# Inverters_drives.net
KiCad netlist of a schematic drawn in Altium Designer
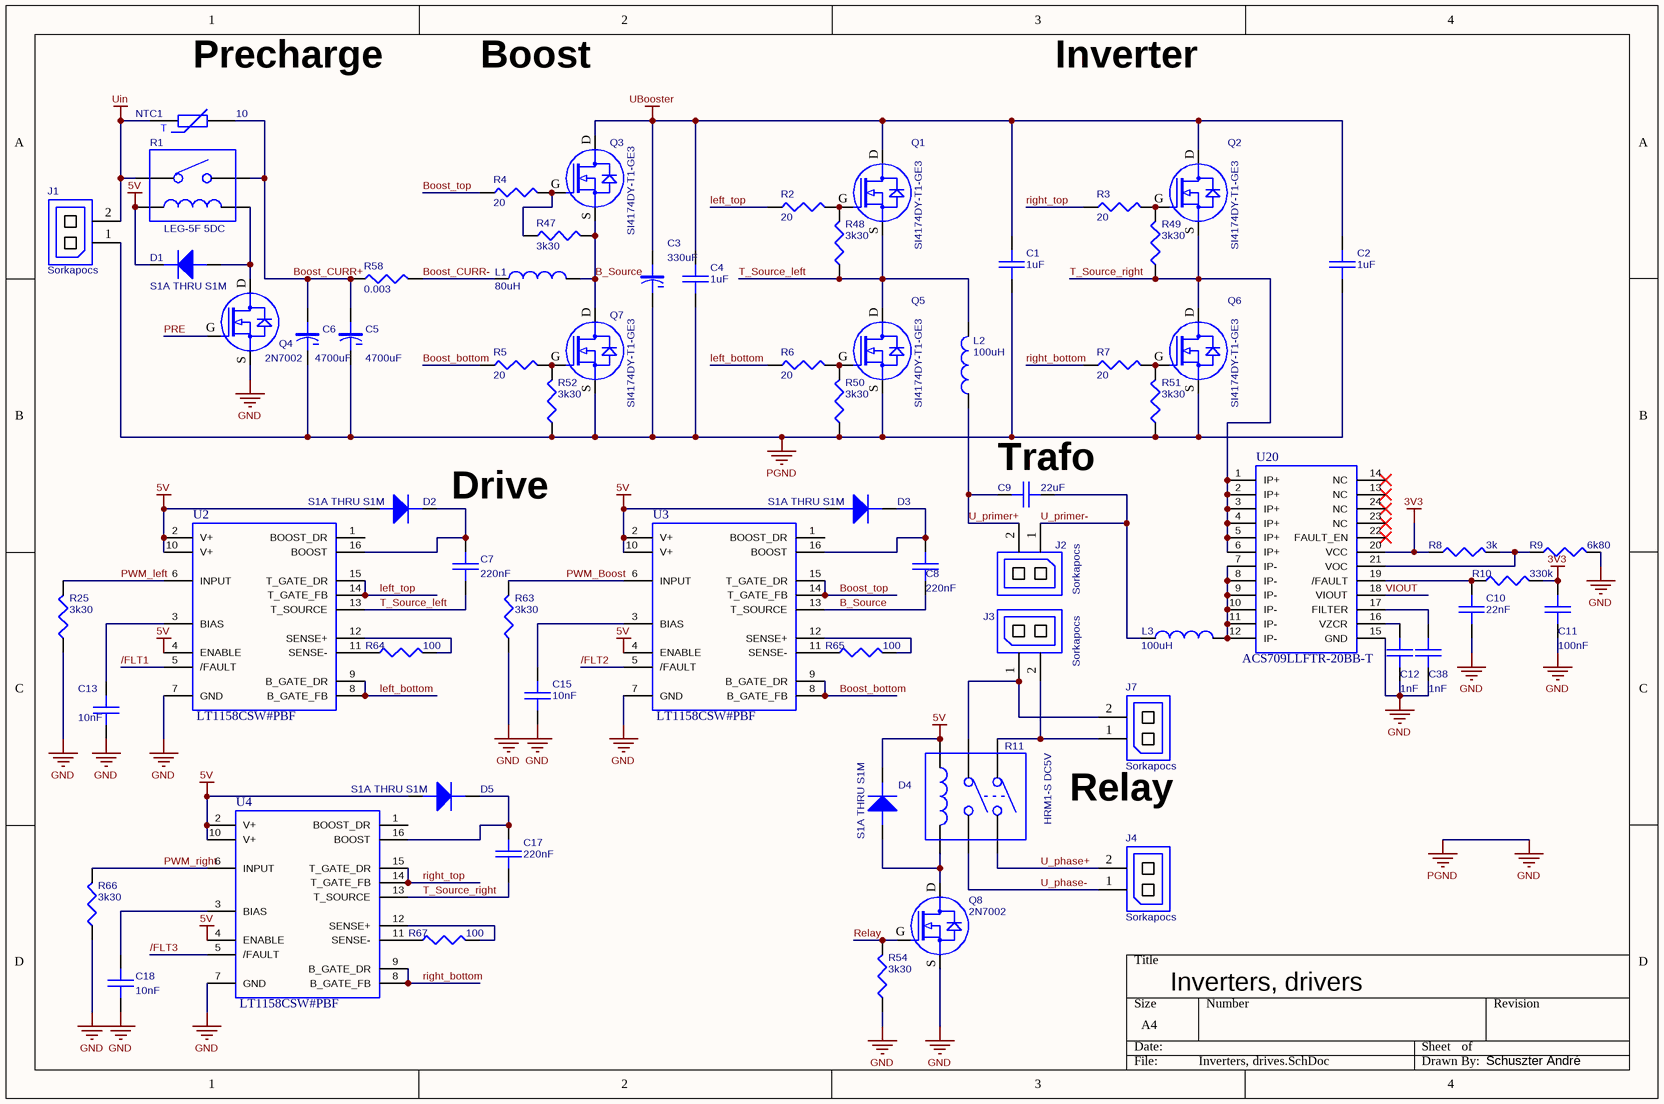
[diagram p0: Inverters, drives.SchDoc]

(export (version "E")
  (design (tool "Eeschema 10.0.6"))
  (components
    (comp (ref "C1")
      (value "1uF")
      (footprint "CAPC3216X07N")
      (description "2495497")
      (fields (field (name "PART NUMBER") "0805F105Z500CT"))
      (libsource (lib "Schlib1") (part "Csnubber"))
    )
    (comp (ref "C2")
      (value "1uF")
      (footprint "CAPC3216X07N")
      (description "2495497")
      (fields (field (name "PART NUMBER") "0805F105Z500CT"))
      (libsource (lib "Schlib1") (part "Csnubber"))
    )
    (comp (ref "C3")
      (value "330uF")
      (footprint "CAPAE116103X105N")
      (description "2611390")
      (fields (field (name "PART NUMBER") "MCVVT035M331GB3L"))
      (libsource (lib "PCB_PASSIVE") (part "CAPAE"))
    )
    (comp (ref "C4")
      (value "1uF")
      (footprint "CAPC3216X07N")
      (description "2495497")
      (fields (field (name "PART NUMBER") "GRM31CR6YA106KA12L"))
      (libsource (lib "Schlib1") (part "Csnubber"))
    )
    (comp (ref "C5")
      (value "4700uF")
      (footprint "CAPAE189170X165N")
      (description "2326365")
      (fields (field (name "PART NUMBER") "EEVFK1C472M"))
      (libsource (lib "PCB_PASSIVE") (part "CAPAE"))
    )
    (comp (ref "C6")
      (value "4700uF")
      (footprint "CAPAE189170X165N")
      (description "2326365")
      (fields (field (name "PART NUMBER") "EEVFK1C472M"))
      (libsource (lib "PCB_PASSIVE") (part "CAPAE"))
    )
    (comp (ref "C7")
      (value "220nF")
      (footprint "CAPC2012X06N")
      (description "82-03-85")
      (libsource (lib "PCB_PASSIVE") (part "CAPC"))
    )
    (comp (ref "C8")
      (value "220nF")
      (footprint "CAPC2012X06N")
      (description "82-03-85")
      (libsource (lib "PCB_PASSIVE") (part "CAPC"))
    )
    (comp (ref "C9")
      (value "22uF")
      (footprint "MKS4D052206F00KYSD")
      (description "07-06-83")
      (fields
        (field (name "PART NUMBER") "22uF 100V RM27.5 10% FOL MKS4 MKS4D052206F00KYSD (WIM) 15x26x31.5mm")
      )
      (libsource (lib "PCB_PASSIVE") (part "CAPC"))
    )
    (comp (ref "C10")
      (value "22nF")
      (footprint "CAPC2012X06N")
      (description "82-00-77")
      (libsource (lib "PCB_PASSIVE") (part "CAPC"))
    )
    (comp (ref "C11")
      (value "100nF")
      (footprint "CAPC2012X06N")
      (description "82-07-32")
      (libsource (lib "PCB_PASSIVE") (part "CAPC"))
    )
    (comp (ref "C12")
      (value "1nF")
      (footprint "CAPC2012X06N")
      (description "82-00-75")
      (libsource (lib "PCB_PASSIVE") (part "CAPC"))
    )
    (comp (ref "C13")
      (value "10nF")
      (footprint "CAPC2012X06N")
      (description "82-05-66")
      (libsource (lib "PCB_PASSIVE") (part "CAPC"))
    )
    (comp (ref "C15")
      (value "10nF")
      (footprint "CAPC2012X06N")
      (description "82-05-66")
      (libsource (lib "PCB_PASSIVE") (part "CAPC"))
    )
    (comp (ref "C17")
      (value "220nF")
      (footprint "CAPC2012X06N")
      (description "82-03-85")
      (libsource (lib "PCB_PASSIVE") (part "CAPC"))
    )
    (comp (ref "C18")
      (value "10nF")
      (footprint "CAPC2012X06N")
      (description "82-05-66")
      (libsource (lib "PCB_PASSIVE") (part "CAPC"))
    )
    (comp (ref "C38")
      (value "1nF")
      (footprint "CAPC2012X06N")
      (description "82-00-75")
      (libsource (lib "PCB_PASSIVE") (part "CAPC"))
    )
    (comp (ref "D1")
      (value "S1A THRU S1M")
      (footprint "DIOM4436X25N")
      (description "83-02-64")
      (fields (field (name "PART NUMBER") "1A 1000V DO-214AC RECT. S1M (YET) SMA"))
      (libsource (lib "Schlib1") (part "RELÉ_DIO"))
    )
    (comp (ref "D2")
      (value "S1A THRU S1M")
      (footprint "DIOM4436X25N")
      (description "83-02-64")
      (fields (field (name "PART NUMBER") "1A 1000V DO-214AC RECT. S1M (YET) SMA"))
      (libsource (lib "Schlib1") (part "RELÉ_DIO"))
    )
    (comp (ref "D3")
      (value "S1A THRU S1M")
      (footprint "DIOM4436X25N")
      (description "83-02-64")
      (fields (field (name "PART NUMBER") "1A 1000V DO-214AC RECT. S1M (YET) SMA"))
      (libsource (lib "Schlib1") (part "RELÉ_DIO"))
    )
    (comp (ref "D4")
      (value "S1A THRU S1M")
      (footprint "DIOM4436X25N")
      (description "83-02-64")
      (fields (field (name "PART NUMBER") "1A 1000V DO-214AC RECT. S1M (YET) SMA"))
      (libsource (lib "Schlib1") (part "RELÉ_DIO"))
    )
    (comp (ref "D5")
      (value "S1A THRU S1M")
      (footprint "DIOM4436X25N")
      (description "83-02-64")
      (fields (field (name "PART NUMBER") "1A 1000V DO-214AC RECT. S1M (YET) SMA"))
      (libsource (lib "Schlib1") (part "RELÉ_DIO"))
    )
    (comp (ref "J1")
      (value "Sorkapocs")
      (footprint "sorkapocs")
      (description "43-07-92")
      (fields (field (name "PART NUMBER") "SORKAPOCS 2 P RM5.08 CLL5.08/2 (STE) h=13.8mm LIFT.2.5mmř 24A"))
      (libsource (lib "Schlib1") (part "Sorkapocs"))
    )
    (comp (ref "J2")
      (value "Sorkapocs")
      (footprint "sorkapocs")
      (description "43-07-92")
      (fields (field (name "PART NUMBER") "SORKAPOCS 2 P RM5.08 CLL5.08/2 (STE) h=13.8mm LIFT.2.5mmř 24A"))
      (libsource (lib "") (part "Sorkapocs_1"))
    )
    (comp (ref "J3")
      (value "Sorkapocs")
      (footprint "sorkapocs")
      (description "43-07-92")
      (fields (field (name "PART NUMBER") "SORKAPOCS 2 P RM5.08 CLL5.08/2 (STE) h=13.8mm LIFT.2.5mmř 24A"))
      (libsource (lib "") (part "Sorkapocs_2"))
    )
    (comp (ref "J4")
      (value "Sorkapocs")
      (footprint "sorkapocs")
      (description "43-07-92")
      (fields (field (name "PART NUMBER") "SORKAPOCS 2 P RM5.08 CLL5.08/2 (STE) h=13.8mm LIFT.2.5mmř 24A"))
      (libsource (lib "") (part "Sorkapocs_2"))
    )
    (comp (ref "J7")
      (value "Sorkapocs")
      (footprint "sorkapocs")
      (description "43-07-92")
      (fields (field (name "PART NUMBER") "SORKAPOCS 2 P RM5.08 CLL5.08/2 (STE) h=13.8mm LIFT.2.5mmř 24A"))
      (libsource (lib "") (part "Sorkapocs_2"))
    )
    (comp (ref "L1") (value "80uH") (footprint "IND_160uH") (libsource (lib "PCB_PASSIVE") (part "IND")))
    (comp (ref "L2") (value "100uH") (footprint "IND_160uH") (libsource (lib "PCB_PASSIVE") (part "IND")))
    (comp (ref "L3") (value "100uH") (footprint "IND_160uH") (libsource (lib "PCB_PASSIVE") (part "IND")))
    (comp (ref "NTC1")
      (value "10")
      (footprint "NTC")
      (description "1688795")
      (fields (field (name "PART NUMBER") "B57153S0100M000"))
      (libsource (lib "Schlib1") (part "NTC"))
    )
    (comp (ref "Q1")
      (value "SI4174DY-T1-GE3")
      (footprint "SOIC8-InvFet")
      (description "1840422")
      (libsource (lib "Schlib1") (part "INVERTER_NFET"))
    )
    (comp (ref "Q2")
      (value "SI4174DY-T1-GE3")
      (footprint "SOIC8-InvFet")
      (description "1840422")
      (libsource (lib "Schlib1") (part "INVERTER_NFET"))
    )
    (comp (ref "Q3")
      (value "SI4174DY-T1-GE3")
      (footprint "SOIC8-InvFet")
      (description "1840422")
      (libsource (lib "Schlib1") (part "INVERTER_NFET"))
    )
    (comp (ref "Q4")
      (value "2N7002")
      (footprint "SOT95P240X111_SGD-3N")
      (description "86-00-97")
      (fields (field (name "PART NUMBER") "2N7002 (NXP) N-FET 60V 0.3A 0.83W Rds>5R SOT-23 ˝12W˝ (SN7002)"))
      (libsource (lib "Schlib1") (part "RELÉ_NFET"))
    )
    (comp (ref "Q5")
      (value "SI4174DY-T1-GE3")
      (footprint "SOIC8-InvFet")
      (description "1840422")
      (libsource (lib "Schlib1") (part "INVERTER_NFET"))
    )
    (comp (ref "Q6")
      (value "SI4174DY-T1-GE3")
      (footprint "SOIC8-InvFet")
      (description "1840422")
      (libsource (lib "Schlib1") (part "INVERTER_NFET"))
    )
    (comp (ref "Q7")
      (value "SI4174DY-T1-GE3")
      (footprint "SOIC8-InvFet")
      (description "1840422")
      (libsource (lib "Schlib1") (part "INVERTER_NFET"))
    )
    (comp (ref "Q8")
      (value "2N7002")
      (footprint "SOT95P240X111_SGD-3N")
      (description "86-00-97")
      (fields (field (name "PART NUMBER") "2N7002 (NXP) N-FET 60V 0.3A 0.83W Rds>5R SOT-23 ˝12W˝ (SN7002)"))
      (libsource (lib "Schlib1") (part "RELÉ_NFET"))
    )
    (comp (ref "R1")
      (value "LEG-5F 5DC")
      (footprint "relay_1")
      (description "42-02-61")
      (fields (field (name "PART NUMBER") "LEG-5F 5DC (RAY) 70R"))
      (libsource (lib "Schlib1") (part "RELÉ_1CSAT"))
    )
    (comp (ref "R2")
      (value "20")
      (footprint "RESC2012X06N")
      (description "81-11-96")
      (libsource (lib "PCB_PASSIVE") (part "RES_US_HOR"))
    )
    (comp (ref "R3")
      (value "20")
      (footprint "RESC2012X06N")
      (description "81-11-96")
      (libsource (lib "PCB_PASSIVE") (part "RES_US_HOR"))
    )
    (comp (ref "R4")
      (value "20")
      (footprint "RESC2012X06N")
      (description "81-11-96")
      (libsource (lib "PCB_PASSIVE") (part "RES_US_HOR"))
    )
    (comp (ref "R5")
      (value "20")
      (footprint "RESC2012X06N")
      (description "81-11-96")
      (libsource (lib "PCB_PASSIVE") (part "RES_US_HOR"))
    )
    (comp (ref "R6")
      (value "20")
      (footprint "RESC2012X06N")
      (description "81-11-96")
      (libsource (lib "PCB_PASSIVE") (part "RES_US_HOR"))
    )
    (comp (ref "R7")
      (value "20")
      (footprint "RESC2012X06N")
      (description "81-11-96")
      (libsource (lib "PCB_PASSIVE") (part "RES_US_HOR"))
    )
    (comp (ref "R8")
      (value "3k")
      (footprint "RESC2012X06N")
      (description "81-16-68")
      (libsource (lib "PCB_PASSIVE") (part "RES_US_HOR"))
    )
    (comp (ref "R9")
      (value "6k80")
      (footprint "RESC2012X06N")
      (description "81-10-97")
      (libsource (lib "PCB_PASSIVE") (part "RES_US_HOR"))
    )
    (comp (ref "R10")
      (value "330k")
      (footprint "RESC2012X06N")
      (description "80-15-29")
      (libsource (lib "PCB_PASSIVE") (part "RES_US_HOR"))
    )
    (comp (ref "R11")
      (value "HRM1-S DC5V")
      (footprint "relay")
      (description "9479937")
      (libsource (lib "Schlib1") (part "RELÉ"))
    )
    (comp (ref "R25")
      (value "3k30")
      (footprint "RESC2012X06N")
      (description "81-10-93")
      (libsource (lib "PCB_PASSIVE") (part "RES_US_HOR"))
    )
    (comp (ref "R47")
      (value "3k30")
      (footprint "RESC2012X06N")
      (description "81-10-93")
      (libsource (lib "PCB_PASSIVE") (part "RES_US_HOR"))
    )
    (comp (ref "R48")
      (value "3k30")
      (footprint "RESC2012X06N")
      (description "81-10-93")
      (libsource (lib "PCB_PASSIVE") (part "RES_US_HOR"))
    )
    (comp (ref "R49")
      (value "3k30")
      (footprint "RESC2012X06N")
      (description "81-10-93")
      (libsource (lib "PCB_PASSIVE") (part "RES_US_HOR"))
    )
    (comp (ref "R50")
      (value "3k30")
      (footprint "RESC2012X06N")
      (description "81-10-93")
      (libsource (lib "PCB_PASSIVE") (part "RES_US_HOR"))
    )
    (comp (ref "R51")
      (value "3k30")
      (footprint "RESC2012X06N")
      (description "81-10-93")
      (libsource (lib "PCB_PASSIVE") (part "RES_US_HOR"))
    )
    (comp (ref "R52")
      (value "3k30")
      (footprint "RESC2012X06N")
      (description "81-10-93")
      (libsource (lib "PCB_PASSIVE") (part "RES_US_HOR"))
    )
    (comp (ref "R54")
      (value "3k30")
      (footprint "RESC2012X06N")
      (description "81-10-93")
      (libsource (lib "PCB_PASSIVE") (part "RES_US_HOR"))
    )
    (comp (ref "R58")
      (value "0.003")
      (footprint "RESC6432X07N")
      (description "2356700")
      (fields (field (name "PART NUMBER") "ERJ-M1WTF3M0U"))
      (libsource (lib "PCB_PASSIVE") (part "RES_US_HOR"))
    )
    (comp (ref "R63")
      (value "3k30")
      (footprint "RESC2012X06N")
      (description "81-10-93")
      (libsource (lib "PCB_PASSIVE") (part "RES_US_HOR"))
    )
    (comp (ref "R64")
      (value "100")
      (footprint "RESC2012X06N")
      (description "81-10-75")
      (libsource (lib "PCB_PASSIVE") (part "RES_US_HOR"))
    )
    (comp (ref "R65")
      (value "100")
      (footprint "RESC2012X06N")
      (description "81-10-75")
      (libsource (lib "PCB_PASSIVE") (part "RES_US_HOR"))
    )
    (comp (ref "R66")
      (value "3k30")
      (footprint "RESC2012X06N")
      (description "81-10-93")
      (libsource (lib "PCB_PASSIVE") (part "RES_US_HOR"))
    )
    (comp (ref "R67")
      (value "100")
      (footprint "RESC2012X06N")
      (description "81-10-75")
      (libsource (lib "PCB_PASSIVE") (part "RES_US_HOR"))
    )
    (comp (ref "U2")
      (value " LT1158CSW#PBF")
      (footprint "SOIC127P1060X265-16N")
      (description "1273473")
      (libsource (lib "Schlib1") (part "meghajtó"))
    )
    (comp (ref "U3")
      (value " LT1158CSW#PBF")
      (footprint "SOIC127P1060X265-16N")
      (description "1273473")
      (libsource (lib "Schlib1") (part "meghajtó"))
    )
    (comp (ref "U4")
      (value " LT1158CSW#PBF")
      (footprint "SOIC127P1060X265-16N")
      (description "1273473")
      (libsource (lib "Schlib1") (part "meghajtó"))
    )
    (comp (ref "U20")
      (value "ACS709LLFTR-20BB-T")
      (footprint "SOP64P600X175-24N")
      (libsource (lib "Schlib1") (part "árammérő"))
    )
  )
  (nets
    (net (code "1") (name "/B_Source") (class "Default")
      (node (ref "C8") (pin "2") (pinfunction "2_2") (pintype "passive"))
      (node (ref "L1") (pin "2") (pinfunction "2_2") (pintype "passive"))
      (node (ref "Q3") (pin "S") (pinfunction "S_S") (pintype "passive"))
      (node (ref "Q7") (pin "D") (pinfunction "D_D") (pintype "passive"))
      (node (ref "R47") (pin "2") (pinfunction "2_2") (pintype "passive"))
      (node (ref "U3") (pin "13") (pinfunction "T_SOURCE_13") (pintype "passive"))
    )
    (net (code "2") (name "/Boost_CURR+") (class "Default")
      (node (ref "C5") (pin "1") (pinfunction "P_1") (pintype "passive"))
      (node (ref "C6") (pin "1") (pinfunction "P_1") (pintype "passive"))
      (node (ref "NTC1") (pin "2") (pinfunction "2_2") (pintype "passive"))
      (node (ref "R1") (pin "4") (pinfunction "1_4") (pintype "passive"))
      (node (ref "R58") (pin "1") (pinfunction "1_1") (pintype "passive"))
    )
    (net (code "3") (name "/Boost_CURR-") (class "Default")
      (node (ref "L1") (pin "1") (pinfunction "1_1") (pintype "passive"))
      (node (ref "R58") (pin "2") (pinfunction "2_2") (pintype "passive"))
    )
    (net (code "4") (name "/Boost_bottom") (class "Default")
      (node (ref "R5") (pin "1") (pinfunction "1_1") (pintype "passive"))
      (node (ref "U3") (pin "8") (pinfunction "B_GATE_FB_8") (pintype "passive"))
      (node (ref "U3") (pin "9") (pinfunction "B_GATE_DR_9") (pintype "passive"))
    )
    (net (code "5") (name "/Boost_top") (class "Default")
      (node (ref "R4") (pin "1") (pinfunction "1_1") (pintype "passive"))
      (node (ref "U3") (pin "14") (pinfunction "T_GATE_FB_14") (pintype "passive"))
      (node (ref "U3") (pin "15") (pinfunction "T_GATE_DR_15") (pintype "passive"))
    )
    (net (code "6") (name "/PRE") (class "Default")
      (node (ref "Q4") (pin "G") (pinfunction "G_G") (pintype "passive"))
    )
    (net (code "7") (name "/PWM_Boost") (class "Default")
      (node (ref "R63") (pin "2") (pinfunction "2_2") (pintype "passive"))
      (node (ref "U3") (pin "6") (pinfunction "INPUT_6") (pintype "passive"))
    )
    (net (code "8") (name "/PWM_left") (class "Default")
      (node (ref "R25") (pin "2") (pinfunction "2_2") (pintype "passive"))
      (node (ref "U2") (pin "6") (pinfunction "INPUT_6") (pintype "passive"))
    )
    (net (code "9") (name "/PWM_right") (class "Default")
      (node (ref "R66") (pin "2") (pinfunction "2_2") (pintype "passive"))
      (node (ref "U4") (pin "6") (pinfunction "INPUT_6") (pintype "passive"))
    )
    (net (code "10") (name "/Relay") (class "Default")
      (node (ref "Q8") (pin "G") (pinfunction "G_G") (pintype "passive"))
      (node (ref "R54") (pin "2") (pinfunction "2_2") (pintype "passive"))
    )
    (net (code "11") (name "/T_Source_left") (class "Default")
      (node (ref "C7") (pin "2") (pinfunction "2_2") (pintype "passive"))
      (node (ref "L2") (pin "2") (pinfunction "2_2") (pintype "passive"))
      (node (ref "Q1") (pin "S") (pinfunction "S_S") (pintype "passive"))
      (node (ref "Q5") (pin "D") (pinfunction "D_D") (pintype "passive"))
      (node (ref "R48") (pin "1") (pinfunction "1_1") (pintype "passive"))
      (node (ref "U2") (pin "13") (pinfunction "T_SOURCE_13") (pintype "passive"))
    )
    (net (code "12") (name "/T_Source_right") (class "Default")
      (node (ref "C17") (pin "2") (pinfunction "2_2") (pintype "passive"))
      (node (ref "Q2") (pin "S") (pinfunction "S_S") (pintype "passive"))
      (node (ref "Q6") (pin "D") (pinfunction "D_D") (pintype "passive"))
      (node (ref "R49") (pin "1") (pinfunction "1_1") (pintype "passive"))
      (node (ref "U20") (pin "1") (pinfunction "IP+_1") (pintype "passive"))
      (node (ref "U20") (pin "2") (pinfunction "IP+_2") (pintype "passive"))
      (node (ref "U20") (pin "3") (pinfunction "IP+_3") (pintype "passive"))
      (node (ref "U20") (pin "4") (pinfunction "IP+_4") (pintype "passive"))
      (node (ref "U20") (pin "5") (pinfunction "IP+_5") (pintype "passive"))
      (node (ref "U20") (pin "6") (pinfunction "IP+_6") (pintype "passive"))
      (node (ref "U4") (pin "13") (pinfunction "T_SOURCE_13") (pintype "passive"))
    )
    (net (code "13") (name "/U_phase+") (class "Default")
      (node (ref "J4") (pin "2") (pinfunction "P2_2") (pintype "passive"))
      (node (ref "R11") (pin "6") (pinfunction "2_6") (pintype "passive"))
    )
    (net (code "14") (name "/U_phase-") (class "Default")
      (node (ref "J4") (pin "1") (pinfunction "P1_1") (pintype "passive"))
      (node (ref "R11") (pin "4") (pinfunction "1_4") (pintype "passive"))
    )
    (net (code "15") (name "/U_primer+") (class "Default")
      (node (ref "C9") (pin "1") (pinfunction "1_1") (pintype "passive"))
      (node (ref "J2") (pin "2") (pinfunction "P2_2") (pintype "passive"))
      (node (ref "L2") (pin "1") (pinfunction "1_1") (pintype "passive"))
    )
    (net (code "16") (name "/U_primer-") (class "Default")
      (node (ref "C9") (pin "2") (pinfunction "2_2") (pintype "passive"))
      (node (ref "J2") (pin "1") (pinfunction "P1_1") (pintype "passive"))
      (node (ref "L3") (pin "1") (pinfunction "1_1") (pintype "passive"))
    )
    (net (code "17") (name "/VIOUT") (class "Default")
      (node (ref "U20") (pin "18") (pinfunction "VIOUT_18") (pintype "passive"))
    )
    (net (code "18") (name "/left_bottom") (class "Default")
      (node (ref "R6") (pin "1") (pinfunction "1_1") (pintype "passive"))
      (node (ref "U2") (pin "8") (pinfunction "B_GATE_FB_8") (pintype "passive"))
      (node (ref "U2") (pin "9") (pinfunction "B_GATE_DR_9") (pintype "passive"))
    )
    (net (code "19") (name "/left_top") (class "Default")
      (node (ref "R2") (pin "1") (pinfunction "1_1") (pintype "passive"))
      (node (ref "U2") (pin "14") (pinfunction "T_GATE_FB_14") (pintype "passive"))
      (node (ref "U2") (pin "15") (pinfunction "T_GATE_DR_15") (pintype "passive"))
    )
    (net (code "20") (name "/right_bottom") (class "Default")
      (node (ref "R7") (pin "1") (pinfunction "1_1") (pintype "passive"))
      (node (ref "U4") (pin "8") (pinfunction "B_GATE_FB_8") (pintype "passive"))
      (node (ref "U4") (pin "9") (pinfunction "B_GATE_DR_9") (pintype "passive"))
    )
    (net (code "21") (name "/right_top") (class "Default")
      (node (ref "R3") (pin "1") (pinfunction "1_1") (pintype "passive"))
      (node (ref "U4") (pin "14") (pinfunction "T_GATE_FB_14") (pintype "passive"))
      (node (ref "U4") (pin "15") (pinfunction "T_GATE_DR_15") (pintype "passive"))
    )
    (net (code "22") (name "/{slash}FLT1") (class "Default")
      (node (ref "U2") (pin "5") (pinfunction "/FAULT_5") (pintype "passive"))
    )
    (net (code "23") (name "/{slash}FLT2") (class "Default")
      (node (ref "U3") (pin "5") (pinfunction "/FAULT_5") (pintype "passive"))
    )
    (net (code "24") (name "/{slash}FLT3") (class "Default")
      (node (ref "U4") (pin "5") (pinfunction "/FAULT_5") (pintype "passive"))
    )
    (net (code "25") (name "3V3") (class "Default")
      (node (ref "C11") (pin "1") (pinfunction "1_1") (pintype "passive"))
      (node (ref "R10") (pin "2") (pinfunction "2_2") (pintype "passive"))
      (node (ref "R8") (pin "1") (pinfunction "1_1") (pintype "passive"))
      (node (ref "U20") (pin "20") (pinfunction "VCC_20") (pintype "passive"))
    )
    (net (code "26") (name "5V") (class "Default")
      (node (ref "D1") (pin "C") (pinfunction "CATHODE_C") (pintype "passive"))
      (node (ref "D2") (pin "A") (pinfunction "ANODE_A") (pintype "passive"))
      (node (ref "D3") (pin "A") (pinfunction "ANODE_A") (pintype "passive"))
      (node (ref "D4") (pin "C") (pinfunction "CATHODE_C") (pintype "passive"))
      (node (ref "D5") (pin "A") (pinfunction "ANODE_A") (pintype "passive"))
      (node (ref "R1") (pin "1") (pinfunction "VCC_1") (pintype "passive"))
      (node (ref "R11") (pin "1") (pinfunction "VCC_1") (pintype "passive"))
      (node (ref "U2") (pin "10") (pinfunction "V+_10") (pintype "passive"))
      (node (ref "U2") (pin "2") (pinfunction "V+_2") (pintype "passive"))
      (node (ref "U2") (pin "4") (pinfunction "ENABLE_4") (pintype "passive"))
      (node (ref "U3") (pin "10") (pinfunction "V+_10") (pintype "passive"))
      (node (ref "U3") (pin "2") (pinfunction "V+_2") (pintype "passive"))
      (node (ref "U3") (pin "4") (pinfunction "ENABLE_4") (pintype "passive"))
      (node (ref "U4") (pin "10") (pinfunction "V+_10") (pintype "passive"))
      (node (ref "U4") (pin "2") (pinfunction "V+_2") (pintype "passive"))
      (node (ref "U4") (pin "4") (pinfunction "ENABLE_4") (pintype "passive"))
    )
    (net (code "27") (name "GND") (class "Default")
      (node (ref "C1") (pin "2") (pinfunction "2_2") (pintype "passive"))
      (node (ref "C10") (pin "2") (pinfunction "2_2") (pintype "passive"))
      (node (ref "C11") (pin "2") (pinfunction "2_2") (pintype "passive"))
      (node (ref "C12") (pin "2") (pinfunction "2_2") (pintype "passive"))
      (node (ref "C13") (pin "2") (pinfunction "2_2") (pintype "passive"))
      (node (ref "C15") (pin "2") (pinfunction "2_2") (pintype "passive"))
      (node (ref "C18") (pin "2") (pinfunction "2_2") (pintype "passive"))
      (node (ref "C2") (pin "2") (pinfunction "2_2") (pintype "passive"))
      (node (ref "C3") (pin "2") (pinfunction "N_2") (pintype "passive"))
      (node (ref "C38") (pin "2") (pinfunction "2_2") (pintype "passive"))
      (node (ref "C4") (pin "2") (pinfunction "2_2") (pintype "passive"))
      (node (ref "C5") (pin "2") (pinfunction "N_2") (pintype "passive"))
      (node (ref "C6") (pin "2") (pinfunction "N_2") (pintype "passive"))
      (node (ref "J1") (pin "1") (pinfunction "P1_1") (pintype "passive"))
      (node (ref "Q4") (pin "S") (pinfunction "S_S") (pintype "passive"))
      (node (ref "Q5") (pin "S") (pinfunction "S_S") (pintype "passive"))
      (node (ref "Q6") (pin "S") (pinfunction "S_S") (pintype "passive"))
      (node (ref "Q7") (pin "S") (pinfunction "S_S") (pintype "passive"))
      (node (ref "Q8") (pin "S") (pinfunction "S_S") (pintype "passive"))
      (node (ref "R25") (pin "1") (pinfunction "1_1") (pintype "passive"))
      (node (ref "R50") (pin "1") (pinfunction "1_1") (pintype "passive"))
      (node (ref "R51") (pin "1") (pinfunction "1_1") (pintype "passive"))
      (node (ref "R52") (pin "1") (pinfunction "1_1") (pintype "passive"))
      (node (ref "R54") (pin "1") (pinfunction "1_1") (pintype "passive"))
      (node (ref "R63") (pin "1") (pinfunction "1_1") (pintype "passive"))
      (node (ref "R66") (pin "1") (pinfunction "1_1") (pintype "passive"))
      (node (ref "R9") (pin "2") (pinfunction "2_2") (pintype "passive"))
      (node (ref "U2") (pin "7") (pinfunction "GND_7") (pintype "passive"))
      (node (ref "U20") (pin "15") (pinfunction "GND_15") (pintype "passive"))
      (node (ref "U3") (pin "7") (pinfunction "GND_7") (pintype "passive"))
      (node (ref "U4") (pin "7") (pinfunction "GND_7") (pintype "passive"))
    )
    (net (code "28") (name "Net-(D1-ANODE)") (class "Default")
      (node (ref "D1") (pin "A") (pinfunction "ANODE_A") (pintype "passive"))
      (node (ref "Q4") (pin "D") (pinfunction "D_D") (pintype "passive"))
      (node (ref "R1") (pin "2") (pinfunction "GND_2") (pintype "passive"))
    )
    (net (code "29") (name "Net-(D2-CATHODE)") (class "Default")
      (node (ref "C7") (pin "1") (pinfunction "1_1") (pintype "passive"))
      (node (ref "D2") (pin "C") (pinfunction "CATHODE_C") (pintype "passive"))
      (node (ref "U2") (pin "16") (pinfunction "BOOST_16") (pintype "passive"))
    )
    (net (code "30") (name "Net-(D3-CATHODE)") (class "Default")
      (node (ref "C8") (pin "1") (pinfunction "1_1") (pintype "passive"))
      (node (ref "D3") (pin "C") (pinfunction "CATHODE_C") (pintype "passive"))
      (node (ref "U3") (pin "16") (pinfunction "BOOST_16") (pintype "passive"))
    )
    (net (code "31") (name "Net-(D4-ANODE)") (class "Default")
      (node (ref "D4") (pin "A") (pinfunction "ANODE_A") (pintype "passive"))
      (node (ref "Q8") (pin "D") (pinfunction "D_D") (pintype "passive"))
      (node (ref "R11") (pin "2") (pinfunction "GND_2") (pintype "passive"))
    )
    (net (code "32") (name "Net-(D5-CATHODE)") (class "Default")
      (node (ref "C17") (pin "1") (pinfunction "1_1") (pintype "passive"))
      (node (ref "D5") (pin "C") (pinfunction "CATHODE_C") (pintype "passive"))
      (node (ref "U4") (pin "16") (pinfunction "BOOST_16") (pintype "passive"))
    )
    (net (code "33") (name "Net-(J3-P1)") (class "Default")
      (node (ref "J3") (pin "1") (pinfunction "P1_1") (pintype "passive"))
      (node (ref "J7") (pin "2") (pinfunction "P2_2") (pintype "passive"))
      (node (ref "R11") (pin "3") (pinfunction "1_3") (pintype "passive"))
    )
    (net (code "34") (name "Net-(J3-P2)") (class "Default")
      (node (ref "J3") (pin "2") (pinfunction "P2_2") (pintype "passive"))
      (node (ref "J7") (pin "1") (pinfunction "P1_1") (pintype "passive"))
      (node (ref "R11") (pin "5") (pinfunction "2_5") (pintype "passive"))
    )
    (net (code "35") (name "Net-(L3-Pad2)") (class "Default")
      (node (ref "L3") (pin "2") (pinfunction "2_2") (pintype "passive"))
      (node (ref "U20") (pin "10") (pinfunction "IP-_10") (pintype "passive"))
      (node (ref "U20") (pin "11") (pinfunction "IP-_11") (pintype "passive"))
      (node (ref "U20") (pin "12") (pinfunction "IP-_12") (pintype "passive"))
      (node (ref "U20") (pin "7") (pinfunction "IP-_7") (pintype "passive"))
      (node (ref "U20") (pin "8") (pinfunction "IP-_8") (pintype "passive"))
      (node (ref "U20") (pin "9") (pinfunction "IP-_9") (pintype "passive"))
    )
    (net (code "36") (name "Net-(Q1-PadG)") (class "Default")
      (node (ref "Q1") (pin "G") (pinfunction "G_G") (pintype "passive"))
      (node (ref "R2") (pin "2") (pinfunction "2_2") (pintype "passive"))
      (node (ref "R48") (pin "2") (pinfunction "2_2") (pintype "passive"))
    )
    (net (code "37") (name "Net-(Q2-PadG)") (class "Default")
      (node (ref "Q2") (pin "G") (pinfunction "G_G") (pintype "passive"))
      (node (ref "R3") (pin "2") (pinfunction "2_2") (pintype "passive"))
      (node (ref "R49") (pin "2") (pinfunction "2_2") (pintype "passive"))
    )
    (net (code "38") (name "Net-(Q3-PadG)") (class "Default")
      (node (ref "Q3") (pin "G") (pinfunction "G_G") (pintype "passive"))
      (node (ref "R4") (pin "2") (pinfunction "2_2") (pintype "passive"))
      (node (ref "R47") (pin "1") (pinfunction "1_1") (pintype "passive"))
    )
    (net (code "39") (name "Net-(Q5-PadG)") (class "Default")
      (node (ref "Q5") (pin "G") (pinfunction "G_G") (pintype "passive"))
      (node (ref "R50") (pin "2") (pinfunction "2_2") (pintype "passive"))
      (node (ref "R6") (pin "2") (pinfunction "2_2") (pintype "passive"))
    )
    (net (code "40") (name "Net-(Q6-PadG)") (class "Default")
      (node (ref "Q6") (pin "G") (pinfunction "G_G") (pintype "passive"))
      (node (ref "R51") (pin "2") (pinfunction "2_2") (pintype "passive"))
      (node (ref "R7") (pin "2") (pinfunction "2_2") (pintype "passive"))
    )
    (net (code "41") (name "Net-(Q7-PadG)") (class "Default")
      (node (ref "Q7") (pin "G") (pinfunction "G_G") (pintype "passive"))
      (node (ref "R5") (pin "2") (pinfunction "2_2") (pintype "passive"))
      (node (ref "R52") (pin "2") (pinfunction "2_2") (pintype "passive"))
    )
    (net (code "42") (name "Net-(U2-BIAS)") (class "Default")
      (node (ref "C13") (pin "1") (pinfunction "1_1") (pintype "passive"))
      (node (ref "U2") (pin "3") (pinfunction "BIAS_3") (pintype "passive"))
    )
    (net (code "43") (name "Net-(U2-SENSE+)") (class "Default")
      (node (ref "R64") (pin "2") (pinfunction "2_2") (pintype "passive"))
      (node (ref "U2") (pin "12") (pinfunction "SENSE+_12") (pintype "passive"))
    )
    (net (code "44") (name "Net-(U2-SENSE-)") (class "Default")
      (node (ref "R64") (pin "1") (pinfunction "1_1") (pintype "passive"))
      (node (ref "U2") (pin "11") (pinfunction "SENSE-_11") (pintype "passive"))
    )
    (net (code "45") (name "Net-(U3-BIAS)") (class "Default")
      (node (ref "C15") (pin "1") (pinfunction "1_1") (pintype "passive"))
      (node (ref "U3") (pin "3") (pinfunction "BIAS_3") (pintype "passive"))
    )
    (net (code "46") (name "Net-(U3-SENSE+)") (class "Default")
      (node (ref "R65") (pin "2") (pinfunction "2_2") (pintype "passive"))
      (node (ref "U3") (pin "12") (pinfunction "SENSE+_12") (pintype "passive"))
    )
    (net (code "47") (name "Net-(U3-SENSE-)") (class "Default")
      (node (ref "R65") (pin "1") (pinfunction "1_1") (pintype "passive"))
      (node (ref "U3") (pin "11") (pinfunction "SENSE-_11") (pintype "passive"))
    )
    (net (code "48") (name "Net-(U4-BIAS)") (class "Default")
      (node (ref "C18") (pin "1") (pinfunction "1_1") (pintype "passive"))
      (node (ref "U4") (pin "3") (pinfunction "BIAS_3") (pintype "passive"))
    )
    (net (code "49") (name "Net-(U4-SENSE+)") (class "Default")
      (node (ref "R67") (pin "2") (pinfunction "2_2") (pintype "passive"))
      (node (ref "U4") (pin "12") (pinfunction "SENSE+_12") (pintype "passive"))
    )
    (net (code "50") (name "Net-(U4-SENSE-)") (class "Default")
      (node (ref "R67") (pin "1") (pinfunction "1_1") (pintype "passive"))
      (node (ref "U4") (pin "11") (pinfunction "SENSE-_11") (pintype "passive"))
    )
    (net (code "51") (name "Net-(U20-FILTER)") (class "Default")
      (node (ref "C38") (pin "1") (pinfunction "1_1") (pintype "passive"))
      (node (ref "U20") (pin "17") (pinfunction "FILTER_17") (pintype "passive"))
    )
    (net (code "52") (name "Net-(U20-VOC)") (class "Default")
      (node (ref "R8") (pin "2") (pinfunction "2_2") (pintype "passive"))
      (node (ref "R9") (pin "1") (pinfunction "1_1") (pintype "passive"))
      (node (ref "U20") (pin "21") (pinfunction "VOC_21") (pintype "passive"))
    )
    (net (code "53") (name "Net-(U20-VZCR)") (class "Default")
      (node (ref "C12") (pin "1") (pinfunction "1_1") (pintype "passive"))
      (node (ref "U20") (pin "16") (pinfunction "VZCR_16") (pintype "passive"))
    )
    (net (code "54") (name "Net-(U20-{slash}FAULT)") (class "Default")
      (node (ref "C10") (pin "1") (pinfunction "1_1") (pintype "passive"))
      (node (ref "R10") (pin "1") (pinfunction "1_1") (pintype "passive"))
      (node (ref "U20") (pin "19") (pinfunction "/FAULT_19") (pintype "passive"))
    )
    (net (code "55") (name "UBooster") (class "Default")
      (node (ref "C1") (pin "1") (pinfunction "1_1") (pintype "passive"))
      (node (ref "C2") (pin "1") (pinfunction "1_1") (pintype "passive"))
      (node (ref "C3") (pin "1") (pinfunction "P_1") (pintype "passive"))
      (node (ref "C4") (pin "1") (pinfunction "1_1") (pintype "passive"))
      (node (ref "Q1") (pin "D") (pinfunction "D_D") (pintype "passive"))
      (node (ref "Q2") (pin "D") (pinfunction "D_D") (pintype "passive"))
      (node (ref "Q3") (pin "D") (pinfunction "D_D") (pintype "passive"))
    )
    (net (code "56") (name "Uin") (class "Default")
      (node (ref "J1") (pin "2") (pinfunction "P2_2") (pintype "passive"))
      (node (ref "NTC1") (pin "1") (pinfunction "1_1") (pintype "passive"))
      (node (ref "R1") (pin "3") (pinfunction "1_3") (pintype "passive"))
    )
    (net (code "57") (name "unconnected-(U2-BOOST_DR-Pad1)") (class "Default")
      (node (ref "U2") (pin "1") (pinfunction "BOOST_DR_1") (pintype "passive"))
    )
    (net (code "58") (name "unconnected-(U3-BOOST_DR-Pad1)") (class "Default")
      (node (ref "U3") (pin "1") (pinfunction "BOOST_DR_1") (pintype "passive"))
    )
    (net (code "59") (name "unconnected-(U4-BOOST_DR-Pad1)") (class "Default")
      (node (ref "U4") (pin "1") (pinfunction "BOOST_DR_1") (pintype "passive"))
    )
    (net (code "60") (name "unconnected-(U20-FAULT_EN-Pad22)") (class "Default")
      (node (ref "U20") (pin "22") (pinfunction "FAULT_EN_22") (pintype "passive+no_connect"))
    )
    (net (code "61") (name "unconnected-(U20-NC-Pad13)") (class "Default")
      (node (ref "U20") (pin "13") (pinfunction "NC_13") (pintype "passive+no_connect"))
    )
    (net (code "62") (name "unconnected-(U20-NC-Pad14)") (class "Default")
      (node (ref "U20") (pin "14") (pinfunction "NC_14") (pintype "passive+no_connect"))
    )
    (net (code "63") (name "unconnected-(U20-NC-Pad23)") (class "Default")
      (node (ref "U20") (pin "23") (pinfunction "NC_23") (pintype "passive+no_connect"))
    )
    (net (code "64") (name "unconnected-(U20-NC-Pad24)") (class "Default")
      (node (ref "U20") (pin "24") (pinfunction "NC_24") (pintype "passive+no_connect"))
    )
  )
)
